# FDL-1_CTRL_v1_0.net
KiCad netlist of a schematic drawn in EAGLE
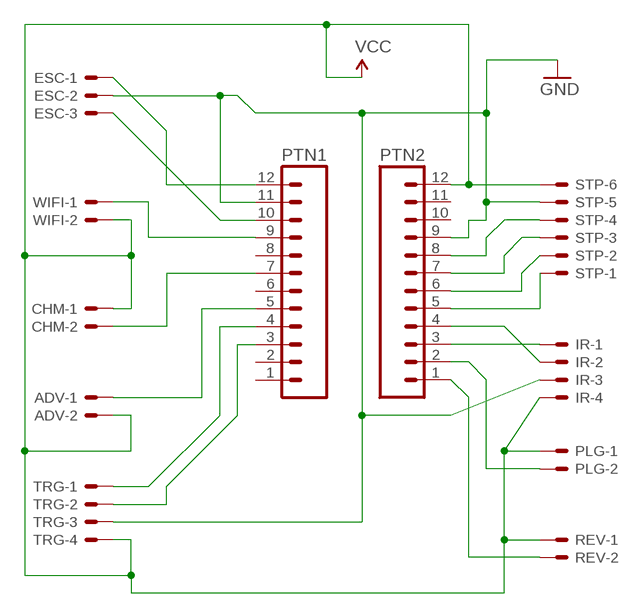
[diagram p0: schematic, sheet 1]

(export (version "E")
  (design (tool "Eeschema 10.0.6"))
  (components
    (comp (ref "ADV")
      (value "JST-XH-02-PIN-LONG-PAD")
      (footprint "eagle-import:JST-XH-02-PACKAGE-LONG-PAD")
      (libsource (lib "eagle-import") (part "JST-XH-02-PIN-LONG-PAD"))
    )
    (comp (ref "CHM")
      (value "JST-XH-02-PIN-LONG-PAD")
      (footprint "eagle-import:JST-XH-02-PACKAGE-LONG-PAD")
      (libsource (lib "eagle-import") (part "JST-XH-02-PIN-LONG-PAD"))
    )
    (comp (ref "ESC")
      (value "JST-XH-03-PIN-LONG-PAD")
      (footprint "eagle-import:JST-XH-03-PACKAGE-LONG-PAD")
      (libsource (lib "eagle-import") (part "JST-XH-03-PIN-LONG-PAD"))
    )
    (comp (ref "IR")
      (value "JST-XH-04-PIN-LONG-PAD")
      (footprint "eagle-import:JST-XH-04-PACKAGE-LONG-PAD")
      (libsource (lib "eagle-import") (part "JST-XH-04-PIN-LONG-PAD"))
    )
    (comp (ref "PLG")
      (value "JST-XH-02-PIN-LONG-PAD")
      (footprint "eagle-import:JST-XH-02-PACKAGE-LONG-PAD")
      (libsource (lib "eagle-import") (part "JST-XH-02-PIN-LONG-PAD"))
    )
    (comp (ref "PTN1")
      (value "M12PTH")
      (footprint "eagle-import:1X12")
      (libsource (lib "eagle-import") (part "M12PTH"))
    )
    (comp (ref "PTN2")
      (value "M12PTH")
      (footprint "eagle-import:1X12")
      (libsource (lib "eagle-import") (part "M12PTH"))
    )
    (comp (ref "REV")
      (value "JST-XH-02-PIN-LONG-PAD")
      (footprint "eagle-import:JST-XH-02-PACKAGE-LONG-PAD")
      (libsource (lib "eagle-import") (part "JST-XH-02-PIN-LONG-PAD"))
    )
    (comp (ref "STP")
      (value "JST-XH-06-PIN-LONG-PAD")
      (footprint "eagle-import:JST-XH-06-PACKAGE-LONG-PAD")
      (libsource (lib "eagle-import") (part "JST-XH-06-PIN-LONG-PAD"))
    )
    (comp (ref "TRG")
      (value "JST-XH-04-PIN-LONG-PAD")
      (footprint "eagle-import:JST-XH-04-PACKAGE-LONG-PAD")
      (libsource (lib "eagle-import") (part "JST-XH-04-PIN-LONG-PAD"))
    )
    (comp (ref "WIFI")
      (value "JST-XH-02-PIN-LONG-PAD")
      (footprint "eagle-import:JST-XH-02-PACKAGE-LONG-PAD")
      (libsource (lib "eagle-import") (part "JST-XH-02-PIN-LONG-PAD"))
    )
  )
  (nets
    (net (code "1") (name "GND") (class "Default")
      (node (ref "ESC") (pin "2") (pinfunction "S_2") (pintype "passive"))
      (node (ref "IR") (pin "3") (pinfunction "S_3") (pintype "passive"))
      (node (ref "PTN1") (pin "11") (pinfunction "11_11") (pintype "passive"))
      (node (ref "PTN2") (pin "9") (pinfunction "9_9") (pintype "passive"))
      (node (ref "STP") (pin "5") (pinfunction "S_5") (pintype "passive"))
      (node (ref "TRG") (pin "3") (pinfunction "S_3") (pintype "passive"))
    )
    (net (code "2") (name "Net-(ADVA-S)") (class "Default")
      (node (ref "ADV") (pin "1") (pinfunction "S_1") (pintype "passive"))
      (node (ref "PTN1") (pin "5") (pinfunction "5_5") (pintype "passive"))
    )
    (net (code "3") (name "Net-(CHMB-S)") (class "Default")
      (node (ref "CHM") (pin "2") (pinfunction "S_2") (pintype "passive"))
      (node (ref "PTN1") (pin "7") (pinfunction "7_7") (pintype "passive"))
    )
    (net (code "4") (name "Net-(ESCA-S)") (class "Default")
      (node (ref "ESC") (pin "1") (pinfunction "S_1") (pintype "passive"))
      (node (ref "PTN1") (pin "12") (pinfunction "12_12") (pintype "passive"))
    )
    (net (code "5") (name "Net-(ESCC-S)") (class "Default")
      (node (ref "ESC") (pin "3") (pinfunction "S_3") (pintype "passive"))
      (node (ref "PTN1") (pin "10") (pinfunction "10_10") (pintype "passive"))
    )
    (net (code "6") (name "Net-(IRA-S)") (class "Default")
      (node (ref "IR") (pin "1") (pinfunction "S_1") (pintype "passive"))
      (node (ref "PTN2") (pin "3") (pinfunction "3_3") (pintype "passive"))
    )
    (net (code "7") (name "Net-(IRB-S)") (class "Default")
      (node (ref "IR") (pin "2") (pinfunction "S_2") (pintype "passive"))
      (node (ref "PTN2") (pin "4") (pinfunction "4_4") (pintype "passive"))
    )
    (net (code "8") (name "Net-(PLGB-S)") (class "Default")
      (node (ref "PLG") (pin "2") (pinfunction "S_2") (pintype "passive"))
      (node (ref "PTN2") (pin "2") (pinfunction "2_2") (pintype "passive"))
    )
    (net (code "9") (name "Net-(REVB-S)") (class "Default")
      (node (ref "PTN2") (pin "1") (pinfunction "1_1") (pintype "passive"))
      (node (ref "REV") (pin "2") (pinfunction "S_2") (pintype "passive"))
    )
    (net (code "10") (name "Net-(STPA-S)") (class "Default")
      (node (ref "PTN2") (pin "5") (pinfunction "5_5") (pintype "passive"))
      (node (ref "STP") (pin "1") (pinfunction "S_1") (pintype "passive"))
    )
    (net (code "11") (name "Net-(STPB-S)") (class "Default")
      (node (ref "PTN2") (pin "6") (pinfunction "6_6") (pintype "passive"))
      (node (ref "STP") (pin "2") (pinfunction "S_2") (pintype "passive"))
    )
    (net (code "12") (name "Net-(STPC-S)") (class "Default")
      (node (ref "PTN2") (pin "7") (pinfunction "7_7") (pintype "passive"))
      (node (ref "STP") (pin "3") (pinfunction "S_3") (pintype "passive"))
    )
    (net (code "13") (name "Net-(STPD-S)") (class "Default")
      (node (ref "PTN2") (pin "8") (pinfunction "8_8") (pintype "passive"))
      (node (ref "STP") (pin "4") (pinfunction "S_4") (pintype "passive"))
    )
    (net (code "14") (name "Net-(TRGA-S)") (class "Default")
      (node (ref "PTN1") (pin "4") (pinfunction "4_4") (pintype "passive"))
      (node (ref "TRG") (pin "1") (pinfunction "S_1") (pintype "passive"))
    )
    (net (code "15") (name "Net-(TRGB-S)") (class "Default")
      (node (ref "PTN1") (pin "3") (pinfunction "3_3") (pintype "passive"))
      (node (ref "TRG") (pin "2") (pinfunction "S_2") (pintype "passive"))
    )
    (net (code "16") (name "Net-(WIFIA-S)") (class "Default")
      (node (ref "PTN1") (pin "9") (pinfunction "9_9") (pintype "passive"))
      (node (ref "WIFI") (pin "1") (pinfunction "S_1") (pintype "passive"))
    )
    (net (code "17") (name "VCC") (class "Default")
      (node (ref "ADV") (pin "2") (pinfunction "S_2") (pintype "passive"))
      (node (ref "CHM") (pin "1") (pinfunction "S_1") (pintype "passive"))
      (node (ref "IR") (pin "4") (pinfunction "S_4") (pintype "passive"))
      (node (ref "PLG") (pin "1") (pinfunction "S_1") (pintype "passive"))
      (node (ref "PTN2") (pin "12") (pinfunction "12_12") (pintype "passive"))
      (node (ref "REV") (pin "1") (pinfunction "S_1") (pintype "passive"))
      (node (ref "STP") (pin "6") (pinfunction "S_6") (pintype "passive"))
      (node (ref "TRG") (pin "4") (pinfunction "S_4") (pintype "passive"))
      (node (ref "WIFI") (pin "2") (pinfunction "S_2") (pintype "passive"))
    )
    (net (code "18") (name "unconnected-(PTN1-Pad1)") (class "Default")
      (node (ref "PTN1") (pin "1") (pinfunction "1_1") (pintype "passive"))
    )
    (net (code "19") (name "unconnected-(PTN1-Pad2)") (class "Default")
      (node (ref "PTN1") (pin "2") (pinfunction "2_2") (pintype "passive"))
    )
    (net (code "20") (name "unconnected-(PTN1-Pad6)") (class "Default")
      (node (ref "PTN1") (pin "6") (pinfunction "6_6") (pintype "passive"))
    )
    (net (code "21") (name "unconnected-(PTN1-Pad8)") (class "Default")
      (node (ref "PTN1") (pin "8") (pinfunction "8_8") (pintype "passive"))
    )
    (net (code "22") (name "unconnected-(PTN2-Pad10)") (class "Default")
      (node (ref "PTN2") (pin "10") (pinfunction "10_10") (pintype "passive"))
    )
    (net (code "23") (name "unconnected-(PTN2-Pad11)") (class "Default")
      (node (ref "PTN2") (pin "11") (pinfunction "11_11") (pintype "passive"))
    )
  )
)
